# 02_J-Link.net
KiCad netlist of a schematic drawn in Altium Designer
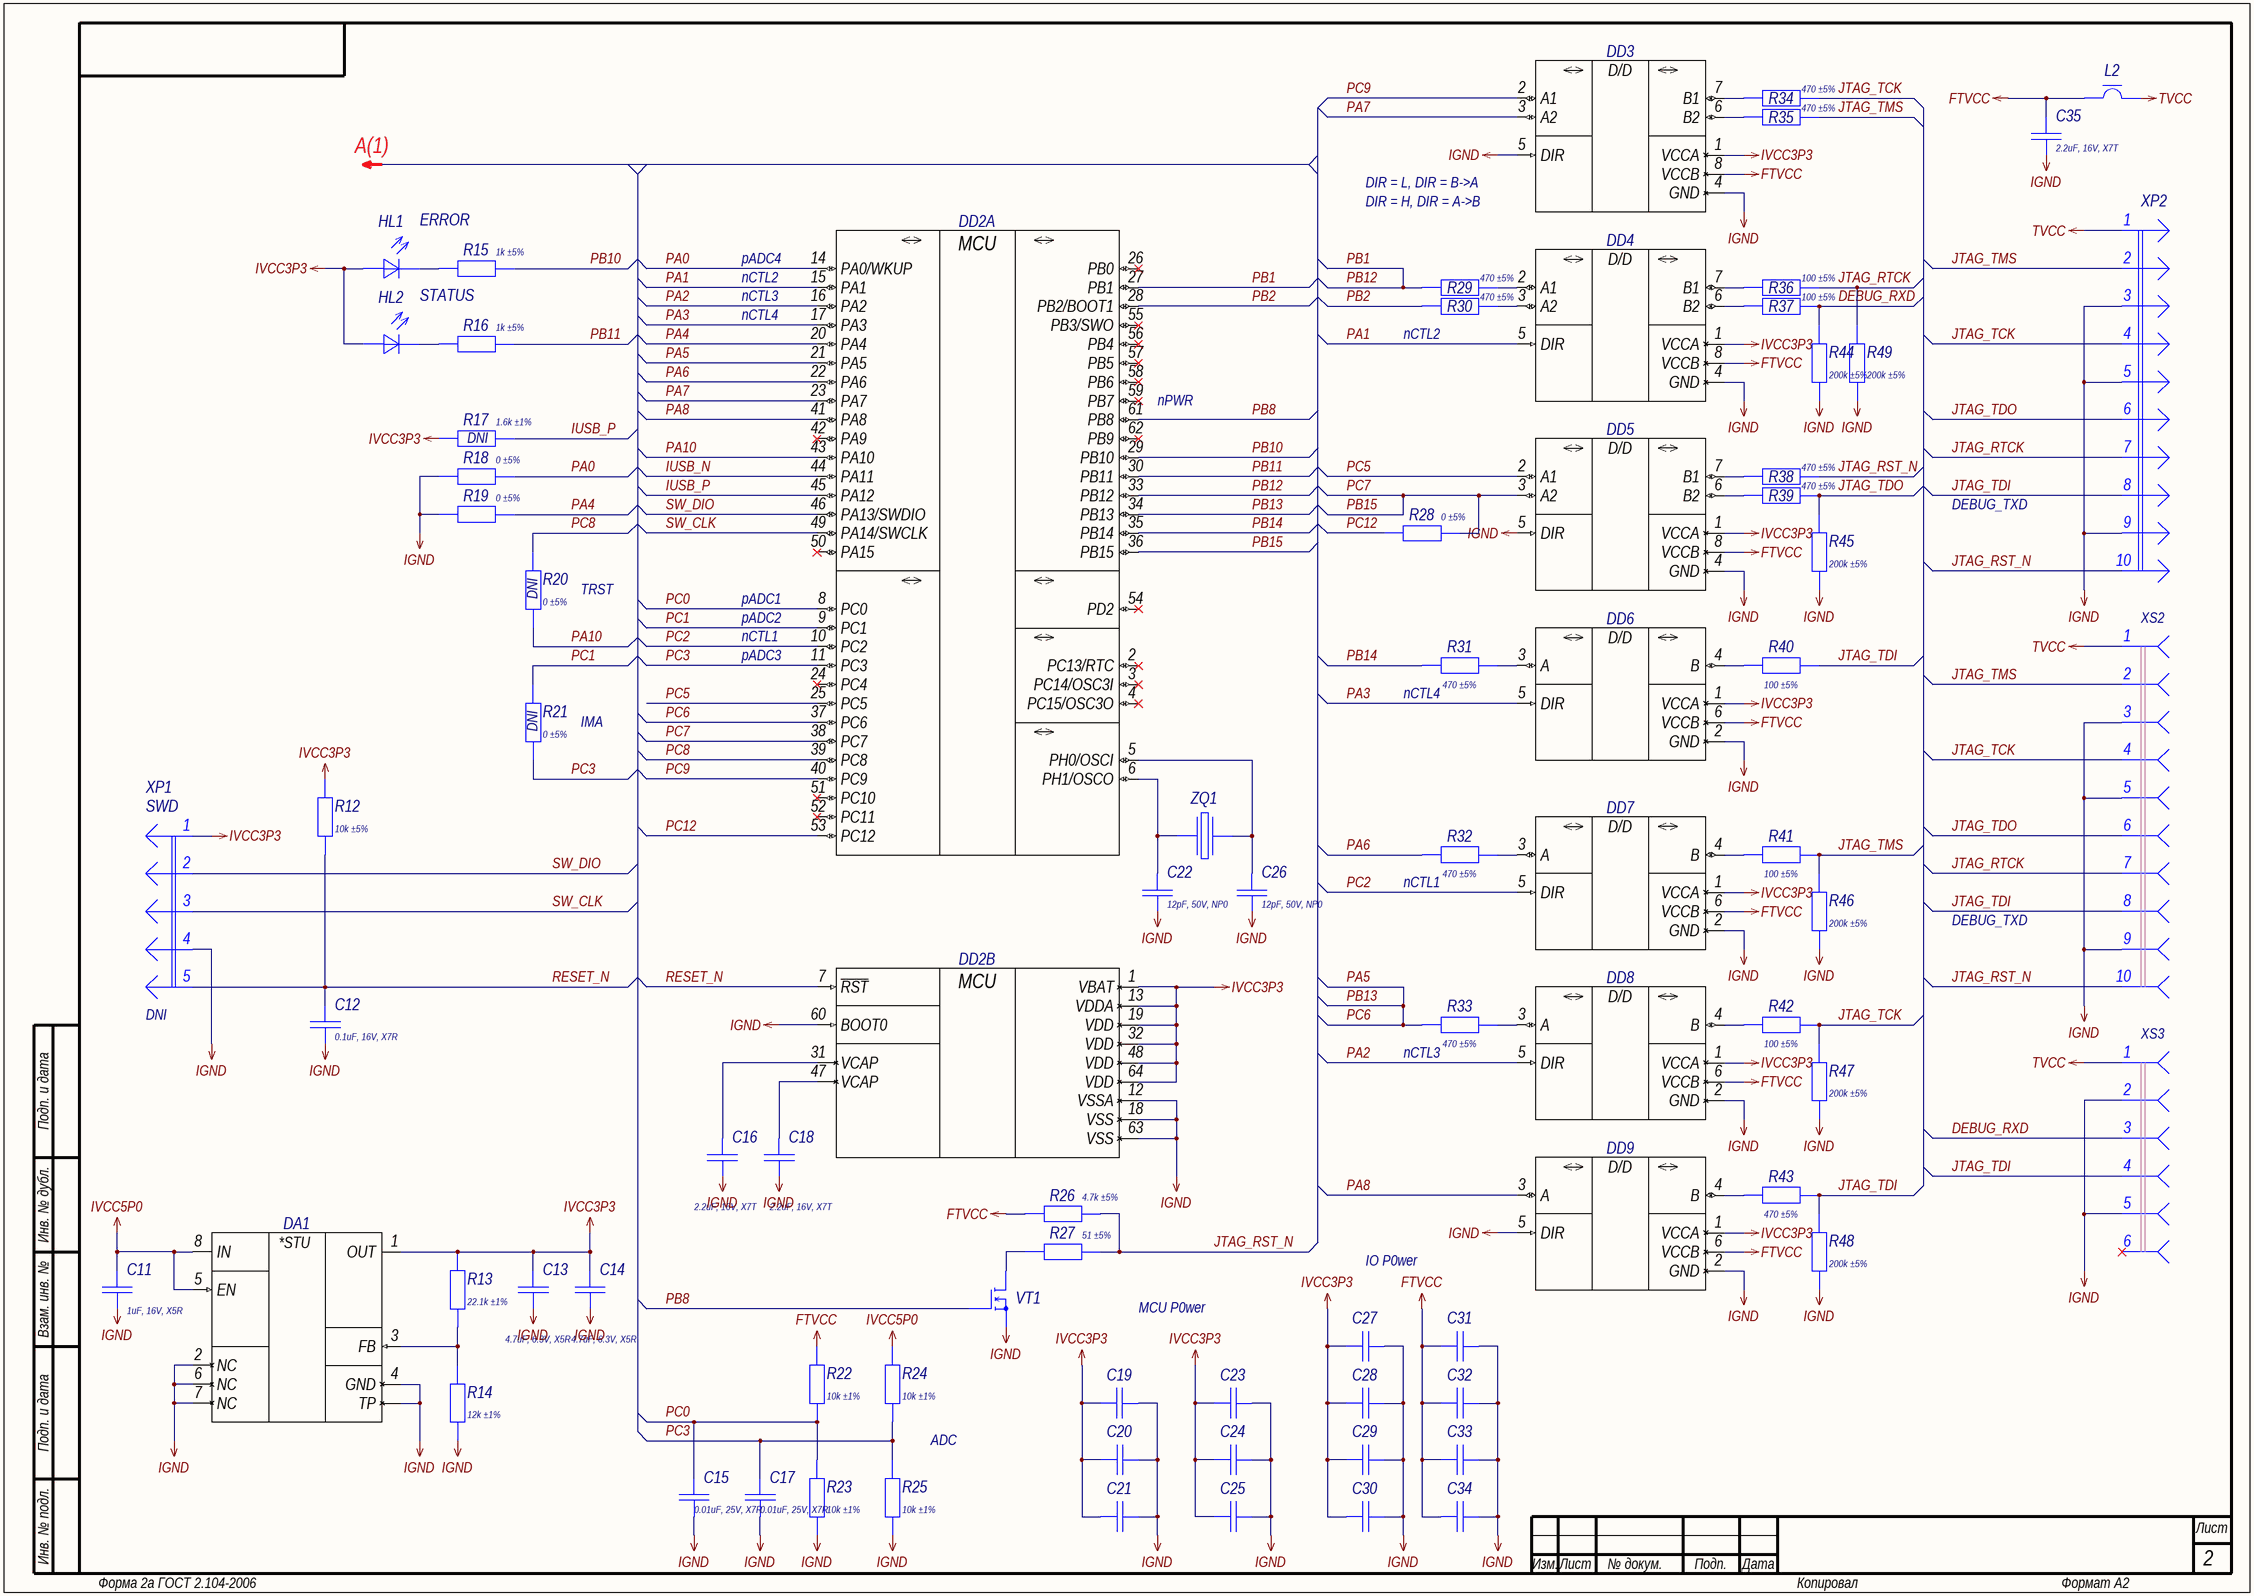
[diagram p0: 02_J-Link.SchDoc]

(export (version "E")
  (design (tool "Eeschema 10.0.6"))
  (components
    (comp (ref "C11")
      (value "Capacitor")
      (footprint "C0402_L")
      (fields
        (field (name "PART NUMBER") "GRM155R61C105KA12D")
        (field (name "VOLTAGE") "16V")
        (field (name "TOLERANCE") "±10%")
        (field (name "SCHEMATIC VALUE") "1uF, 16V, X5R")
      )
      (libsource (lib "ADLib") (part "Capacitor"))
    )
    (comp (ref "C12")
      (value "Capacitor")
      (footprint "C0402_L")
      (fields
        (field (name "PART NUMBER") "GCM155R71C104KA55D")
        (field (name "VOLTAGE") "16V")
        (field (name "TOLERANCE") "±10%")
        (field (name "SCHEMATIC VALUE") "0.1uF, 16V, X7R")
      )
      (libsource (lib "ADLib") (part "Capacitor"))
    )
    (comp (ref "C13")
      (value "Capacitor")
      (footprint "C0402_L")
      (fields
        (field (name "PART NUMBER") "GRM155R60J475ME87D")
        (field (name "VOLTAGE") "6.3V")
        (field (name "TOLERANCE") "±20%")
        (field (name "SCHEMATIC VALUE") "4.7uF, 6.3V, X5R")
      )
      (libsource (lib "ADLib") (part "Capacitor"))
    )
    (comp (ref "C14")
      (value "Capacitor")
      (footprint "C0402_L")
      (fields
        (field (name "PART NUMBER") "GRM155R60J475ME87D")
        (field (name "VOLTAGE") "6.3V")
        (field (name "TOLERANCE") "±20%")
        (field (name "SCHEMATIC VALUE") "4.7uF, 6.3V, X5R")
      )
      (libsource (lib "ADLib") (part "Capacitor"))
    )
    (comp (ref "C15")
      (value "Capacitor")
      (footprint "C0402_L")
      (fields
        (field (name "PART NUMBER") "GCM155R71E103KA37D")
        (field (name "VOLTAGE") "25V")
        (field (name "TOLERANCE") "±10%")
        (field (name "SCHEMATIC VALUE") "0.01uF, 25V, X7R")
      )
      (libsource (lib "ADLib") (part "Capacitor"))
    )
    (comp (ref "C16")
      (value "Capacitor")
      (footprint "C0402_L")
      (fields
        (field (name "PART NUMBER") "GRM155D71C225ME11D")
        (field (name "VOLTAGE") "16V")
        (field (name "TOLERANCE") "±20%")
        (field (name "SCHEMATIC VALUE") "2.2uF, 16V, X7T")
      )
      (libsource (lib "ADLib") (part "Capacitor"))
    )
    (comp (ref "C17")
      (value "Capacitor")
      (footprint "C0402_L")
      (fields
        (field (name "PART NUMBER") "GCM155R71E103KA37D")
        (field (name "VOLTAGE") "25V")
        (field (name "TOLERANCE") "±10%")
        (field (name "SCHEMATIC VALUE") "0.01uF, 25V, X7R")
      )
      (libsource (lib "ADLib") (part "Capacitor"))
    )
    (comp (ref "C18")
      (value "Capacitor")
      (footprint "C0402_L")
      (fields
        (field (name "PART NUMBER") "GRM155D71C225ME11D")
        (field (name "VOLTAGE") "16V")
        (field (name "TOLERANCE") "±20%")
        (field (name "SCHEMATIC VALUE") "2.2uF, 16V, X7T")
      )
      (libsource (lib "ADLib") (part "Capacitor"))
    )
    (comp (ref "C19")
      (value "Capacitor")
      (footprint "C0402_L")
      (fields
        (field (name "PART NUMBER") "GRM155R60J475ME87D")
        (field (name "VOLTAGE") "6.3V")
        (field (name "TOLERANCE") "±20%")
      )
      (libsource (lib "ADLib") (part "Capacitor"))
    )
    (comp (ref "C20")
      (value "Capacitor")
      (footprint "C0402_L")
      (fields
        (field (name "PART NUMBER") "GCM155R71C104KA55D")
        (field (name "VOLTAGE") "16V")
        (field (name "TOLERANCE") "±10%")
      )
      (libsource (lib "ADLib") (part "Capacitor"))
    )
    (comp (ref "C21")
      (value "Capacitor")
      (footprint "C0402_L")
      (fields
        (field (name "PART NUMBER") "GCM155R71C104KA55D")
        (field (name "VOLTAGE") "16V")
        (field (name "TOLERANCE") "±10%")
      )
      (libsource (lib "ADLib") (part "Capacitor"))
    )
    (comp (ref "C22")
      (value "Capacitor")
      (footprint "C0402_L")
      (fields
        (field (name "PART NUMBER") "GRM1555C1H120JA01D")
        (field (name "VOLTAGE") "50V")
        (field (name "TOLERANCE") "±5%")
        (field (name "SCHEMATIC VALUE") "12pF, 50V, NP0")
      )
      (libsource (lib "ADLib") (part "Capacitor"))
    )
    (comp (ref "C23")
      (value "Capacitor")
      (footprint "C0402_L")
      (fields
        (field (name "PART NUMBER") "GCM155R71C104KA55D")
        (field (name "VOLTAGE") "16V")
        (field (name "TOLERANCE") "±10%")
      )
      (libsource (lib "ADLib") (part "Capacitor"))
    )
    (comp (ref "C24")
      (value "Capacitor")
      (footprint "C0402_L")
      (fields
        (field (name "PART NUMBER") "GCM155R71C104KA55D")
        (field (name "VOLTAGE") "16V")
        (field (name "TOLERANCE") "±10%")
      )
      (libsource (lib "ADLib") (part "Capacitor"))
    )
    (comp (ref "C25")
      (value "Capacitor")
      (footprint "C0402_L")
      (fields
        (field (name "PART NUMBER") "GCM155R71C104KA55D")
        (field (name "VOLTAGE") "16V")
        (field (name "TOLERANCE") "±10%")
      )
      (libsource (lib "ADLib") (part "Capacitor"))
    )
    (comp (ref "C26")
      (value "Capacitor")
      (footprint "C0402_L")
      (fields
        (field (name "PART NUMBER") "GRM1555C1H120JA01D")
        (field (name "VOLTAGE") "50V")
        (field (name "TOLERANCE") "±5%")
        (field (name "SCHEMATIC VALUE") "12pF, 50V, NP0")
      )
      (libsource (lib "ADLib") (part "Capacitor"))
    )
    (comp (ref "C27")
      (value "Capacitor")
      (footprint "C0402_L")
      (fields
        (field (name "PART NUMBER") "GCM155R71C104KA55D")
        (field (name "VOLTAGE") "16V")
        (field (name "TOLERANCE") "±10%")
      )
      (libsource (lib "ADLib") (part "Capacitor"))
    )
    (comp (ref "C28")
      (value "Capacitor")
      (footprint "C0402_L")
      (fields
        (field (name "PART NUMBER") "GCM155R71C104KA55D")
        (field (name "VOLTAGE") "16V")
        (field (name "TOLERANCE") "±10%")
      )
      (libsource (lib "ADLib") (part "Capacitor"))
    )
    (comp (ref "C29")
      (value "Capacitor")
      (footprint "C0402_L")
      (fields
        (field (name "PART NUMBER") "GCM155R71C104KA55D")
        (field (name "VOLTAGE") "16V")
        (field (name "TOLERANCE") "±10%")
      )
      (libsource (lib "ADLib") (part "Capacitor"))
    )
    (comp (ref "C30")
      (value "Capacitor")
      (footprint "C0402_L")
      (fields
        (field (name "PART NUMBER") "GCM155R71C104KA55D")
        (field (name "VOLTAGE") "16V")
        (field (name "TOLERANCE") "±10%")
      )
      (libsource (lib "ADLib") (part "Capacitor"))
    )
    (comp (ref "C31")
      (value "Capacitor")
      (footprint "C0402_L")
      (fields
        (field (name "PART NUMBER") "GCM155R71C104KA55D")
        (field (name "VOLTAGE") "16V")
        (field (name "TOLERANCE") "±10%")
      )
      (libsource (lib "ADLib") (part "Capacitor"))
    )
    (comp (ref "C32")
      (value "Capacitor")
      (footprint "C0402_L")
      (fields
        (field (name "PART NUMBER") "GCM155R71C104KA55D")
        (field (name "VOLTAGE") "16V")
        (field (name "TOLERANCE") "±10%")
      )
      (libsource (lib "ADLib") (part "Capacitor"))
    )
    (comp (ref "C33")
      (value "Capacitor")
      (footprint "C0402_L")
      (fields
        (field (name "PART NUMBER") "GCM155R71C104KA55D")
        (field (name "VOLTAGE") "16V")
        (field (name "TOLERANCE") "±10%")
      )
      (libsource (lib "ADLib") (part "Capacitor"))
    )
    (comp (ref "C34")
      (value "Capacitor")
      (footprint "C0402_L")
      (fields
        (field (name "PART NUMBER") "GCM155R71C104KA55D")
        (field (name "VOLTAGE") "16V")
        (field (name "TOLERANCE") "±10%")
      )
      (libsource (lib "ADLib") (part "Capacitor"))
    )
    (comp (ref "C35")
      (value "Capacitor")
      (footprint "C0402_L")
      (fields
        (field (name "PART NUMBER") "GRM155D71C225ME11D")
        (field (name "VOLTAGE") "16V")
        (field (name "TOLERANCE") "±20%")
        (field (name "SCHEMATIC VALUE") "2.2uF, 16V, X7T")
      )
      (libsource (lib "ADLib") (part "Capacitor"))
    )
    (comp (ref "DA1")
      (value "TPS73701DRB")
      (footprint "VSON-8_065P300X300X100_N")
      (fields (field (name "PART NUMBER") "TPS73701DRBR") (field (name "MANUFACTURER") "Texas Instruments"))
      (libsource (lib "ADLib") (part "TPS73701DRB"))
    )
    (comp (ref "DD2")
      (value "STM32F205RxTx-Series")
      (footprint "LQFP-64_050P1000X1000X160_N")
      (fields (field (name "PART NUMBER") "STM32F205RET6") (field (name "MANUFACTURER") "STMicroelectronics"))
      (libsource (lib "ADLib") (part "STM32F205RxTx-Series"))
    )
    (comp (ref "DD3")
      (value "SN74LVC2T45DCx-Series")
      (footprint "VSSOP-8_050P200X230X090_N")
      (fields
        (field (name "PART NUMBER") "SN74LVC2T45DCUR")
        (field (name "MANUFACTURER") "Texas Instruments")
      )
      (libsource (lib "ADLib") (part "SN74LVC2T45DCx-Series"))
    )
    (comp (ref "DD4")
      (value "SN74LVC2T45DCx-Series")
      (footprint "VSSOP-8_050P200X230X090_N")
      (fields
        (field (name "PART NUMBER") "SN74LVC2T45DCUR")
        (field (name "MANUFACTURER") "Texas Instruments")
      )
      (libsource (lib "ADLib") (part "SN74LVC2T45DCx-Series"))
    )
    (comp (ref "DD5")
      (value "SN74LVC2T45DCx-Series")
      (footprint "VSSOP-8_050P200X230X090_N")
      (fields
        (field (name "PART NUMBER") "SN74LVC2T45DCUR")
        (field (name "MANUFACTURER") "Texas Instruments")
      )
      (libsource (lib "ADLib") (part "SN74LVC2T45DCx-Series"))
    )
    (comp (ref "DD6")
      (value "74LVC1T45x-Series")
      (footprint "X2-DFN-6_050P140X100X040_N")
      (fields
        (field (name "PART NUMBER") "74LVC1T45FZ4-7")
        (field (name "MANUFACTURER") "Diodes Incorporated")
      )
      (libsource (lib "ADLib") (part "74LVC1T45x-Series"))
    )
    (comp (ref "DD7")
      (value "74LVC1T45x-Series")
      (footprint "X2-DFN-6_050P140X100X040_N")
      (fields
        (field (name "PART NUMBER") "74LVC1T45FZ4-7")
        (field (name "MANUFACTURER") "Diodes Incorporated")
      )
      (libsource (lib "ADLib") (part "74LVC1T45x-Series"))
    )
    (comp (ref "DD8")
      (value "74LVC1T45x-Series")
      (footprint "X2-DFN-6_050P140X100X040_N")
      (fields
        (field (name "PART NUMBER") "74LVC1T45FZ4-7")
        (field (name "MANUFACTURER") "Diodes Incorporated")
      )
      (libsource (lib "ADLib") (part "74LVC1T45x-Series"))
    )
    (comp (ref "DD9")
      (value "74LVC1T45x-Series")
      (footprint "X2-DFN-6_050P140X100X040_N")
      (fields
        (field (name "PART NUMBER") "74LVC1T45FZ4-7")
        (field (name "MANUFACTURER") "Diodes Incorporated")
      )
      (libsource (lib "ADLib") (part "74LVC1T45x-Series"))
    )
    (comp (ref "HL1")
      (value "ERROR")
      (footprint "LD0402_L")
      (fields (field (name "PART NUMBER") "KPHHS-1005SURCK") (field (name "MANUFACTURER") "Kingbright"))
      (libsource (lib "ADLib") (part "Led-1"))
    )
    (comp (ref "HL2")
      (value "STATUS")
      (footprint "LD0402_L")
      (fields (field (name "PART NUMBER") "KPHHS-1005QBC-D-V") (field (name "MANUFACTURER") "Kingbright"))
      (libsource (lib "ADLib") (part "Led-1"))
    )
    (comp (ref "L2")
      (value "FerriteBead")
      (footprint "L0402_L")
      (fields
        (field (name "PART NUMBER") "BLM15PD121SN1D")
        (field (name "TOLERANCE") "±25%")
        (field (name "MANUFACTURER") "Murata")
      )
      (libsource (lib "ADLib") (part "FerriteBead"))
    )
    (comp (ref "R12")
      (value "Resistor")
      (footprint "R0402_L")
      (fields
        (field (name "PART NUMBER") "RC0402JR-0710KL")
        (field (name "TOLERANCE") "±5%")
        (field (name "MANUFACTURER") "Yageo")
        (field (name "SCHEMATIC VALUE") "10k ±5%")
      )
      (libsource (lib "ADLib") (part "Resistor"))
    )
    (comp (ref "R13")
      (value "Resistor")
      (footprint "R0402_L")
      (fields
        (field (name "PART NUMBER") "RC0402FR-0722K1L")
        (field (name "TOLERANCE") "±1%")
        (field (name "MANUFACTURER") "Yageo")
        (field (name "SCHEMATIC VALUE") "22.1k ±1%")
      )
      (libsource (lib "ADLib") (part "Resistor"))
    )
    (comp (ref "R14")
      (value "Resistor")
      (footprint "R0402_L")
      (fields
        (field (name "PART NUMBER") "RC0402FR-0712KL")
        (field (name "TOLERANCE") "±1%")
        (field (name "MANUFACTURER") "Yageo")
        (field (name "SCHEMATIC VALUE") "12k ±1%")
      )
      (libsource (lib "ADLib") (part "Resistor"))
    )
    (comp (ref "R15")
      (value "Resistor")
      (footprint "R0402_L")
      (fields
        (field (name "PART NUMBER") "RC0402JR-071KL")
        (field (name "TOLERANCE") "±5%")
        (field (name "MANUFACTURER") "Yageo")
        (field (name "SCHEMATIC VALUE") "1k ±5%")
      )
      (libsource (lib "ADLib") (part "Resistor"))
    )
    (comp (ref "R16")
      (value "Resistor")
      (footprint "R0402_L")
      (fields
        (field (name "PART NUMBER") "RC0402JR-071KL")
        (field (name "TOLERANCE") "±5%")
        (field (name "MANUFACTURER") "Yageo")
        (field (name "SCHEMATIC VALUE") "1k ±5%")
      )
      (libsource (lib "ADLib") (part "Resistor"))
    )
    (comp (ref "R17")
      (value "Resistor")
      (footprint "R0402_L")
      (fields
        (field (name "PART NUMBER") "RC0402FR-071K6L")
        (field (name "TOLERANCE") "±1%")
        (field (name "MANUFACTURER") "Yageo")
        (field (name "SCHEMATIC VALUE") "1.6k ±1%")
      )
      (libsource (lib "ADLib") (part "Resistor"))
    )
    (comp (ref "R18")
      (value "Resistor")
      (footprint "R0402_L")
      (fields
        (field (name "PART NUMBER") "RC0402JR-070RL")
        (field (name "TOLERANCE") "±5%")
        (field (name "MANUFACTURER") "Yageo")
        (field (name "SCHEMATIC VALUE") "0 ±5%")
      )
      (libsource (lib "ADLib") (part "Resistor"))
    )
    (comp (ref "R19")
      (value "Resistor")
      (footprint "R0402_L")
      (fields
        (field (name "PART NUMBER") "RC0402JR-070RL")
        (field (name "TOLERANCE") "±5%")
        (field (name "MANUFACTURER") "Yageo")
        (field (name "SCHEMATIC VALUE") "0 ±5%")
      )
      (libsource (lib "ADLib") (part "Resistor"))
    )
    (comp (ref "R20")
      (value "Resistor")
      (footprint "R0402_L")
      (fields
        (field (name "PART NUMBER") "RC0402JR-070RL")
        (field (name "TOLERANCE") "±5%")
        (field (name "MANUFACTURER") "Yageo")
        (field (name "SCHEMATIC VALUE") "0 ±5%")
      )
      (libsource (lib "ADLib") (part "Resistor"))
    )
    (comp (ref "R21")
      (value "Resistor")
      (footprint "R0402_L")
      (fields
        (field (name "PART NUMBER") "RC0402JR-070RL")
        (field (name "TOLERANCE") "±5%")
        (field (name "MANUFACTURER") "Yageo")
        (field (name "SCHEMATIC VALUE") "0 ±5%")
      )
      (libsource (lib "ADLib") (part "Resistor"))
    )
    (comp (ref "R22")
      (value "Resistor")
      (footprint "R0402_L")
      (fields
        (field (name "PART NUMBER") "RC0402FR-0710KL")
        (field (name "TOLERANCE") "±1%")
        (field (name "MANUFACTURER") "Yageo")
        (field (name "SCHEMATIC VALUE") "10k ±1%")
      )
      (libsource (lib "ADLib") (part "Resistor"))
    )
    (comp (ref "R23")
      (value "Resistor")
      (footprint "R0402_L")
      (fields
        (field (name "PART NUMBER") "RC0402FR-0710KL")
        (field (name "TOLERANCE") "±1%")
        (field (name "MANUFACTURER") "Yageo")
        (field (name "SCHEMATIC VALUE") "10k ±1%")
      )
      (libsource (lib "ADLib") (part "Resistor"))
    )
    (comp (ref "R24")
      (value "Resistor")
      (footprint "R0402_L")
      (fields
        (field (name "PART NUMBER") "RC0402FR-0710KL")
        (field (name "TOLERANCE") "±1%")
        (field (name "MANUFACTURER") "Yageo")
        (field (name "SCHEMATIC VALUE") "10k ±1%")
      )
      (libsource (lib "ADLib") (part "Resistor"))
    )
    (comp (ref "R25")
      (value "Resistor")
      (footprint "R0402_L")
      (fields
        (field (name "PART NUMBER") "RC0402FR-0710KL")
        (field (name "TOLERANCE") "±1%")
        (field (name "MANUFACTURER") "Yageo")
        (field (name "SCHEMATIC VALUE") "10k ±1%")
      )
      (libsource (lib "ADLib") (part "Resistor"))
    )
    (comp (ref "R26")
      (value "Resistor")
      (footprint "R0402_L")
      (fields
        (field (name "PART NUMBER") "RC0402JR-074K7L")
        (field (name "TOLERANCE") "±5%")
        (field (name "MANUFACTURER") "Yageo")
        (field (name "SCHEMATIC VALUE") "4.7k ±5%")
      )
      (libsource (lib "ADLib") (part "Resistor"))
    )
    (comp (ref "R27")
      (value "Resistor")
      (footprint "R0402_L")
      (fields
        (field (name "PART NUMBER") "RC0402JR-0751RL")
        (field (name "TOLERANCE") "±5%")
        (field (name "MANUFACTURER") "Yageo")
        (field (name "SCHEMATIC VALUE") "51 ±5%")
      )
      (libsource (lib "ADLib") (part "Resistor"))
    )
    (comp (ref "R28")
      (value "Resistor")
      (footprint "R0402_L")
      (fields
        (field (name "PART NUMBER") "RC0402JR-070RL")
        (field (name "TOLERANCE") "±5%")
        (field (name "MANUFACTURER") "Yageo")
        (field (name "SCHEMATIC VALUE") "0 ±5%")
      )
      (libsource (lib "ADLib") (part "Resistor"))
    )
    (comp (ref "R29")
      (value "Resistor")
      (footprint "R0402_L")
      (fields
        (field (name "PART NUMBER") "RC0402JR-07470RL")
        (field (name "TOLERANCE") "±5%")
        (field (name "MANUFACTURER") "Yageo")
        (field (name "SCHEMATIC VALUE") "470 ±5%")
      )
      (libsource (lib "ADLib") (part "Resistor"))
    )
    (comp (ref "R30")
      (value "Resistor")
      (footprint "R0402_L")
      (fields
        (field (name "PART NUMBER") "RC0402JR-07470RL")
        (field (name "TOLERANCE") "±5%")
        (field (name "MANUFACTURER") "Yageo")
        (field (name "SCHEMATIC VALUE") "470 ±5%")
      )
      (libsource (lib "ADLib") (part "Resistor"))
    )
    (comp (ref "R31")
      (value "Resistor")
      (footprint "R0402_L")
      (fields
        (field (name "PART NUMBER") "RC0402JR-07470RL")
        (field (name "TOLERANCE") "±5%")
        (field (name "MANUFACTURER") "Yageo")
        (field (name "SCHEMATIC VALUE") "470 ±5%")
      )
      (libsource (lib "ADLib") (part "Resistor"))
    )
    (comp (ref "R32")
      (value "Resistor")
      (footprint "R0402_L")
      (fields
        (field (name "PART NUMBER") "RC0402JR-07470RL")
        (field (name "TOLERANCE") "±5%")
        (field (name "MANUFACTURER") "Yageo")
        (field (name "SCHEMATIC VALUE") "470 ±5%")
      )
      (libsource (lib "ADLib") (part "Resistor"))
    )
    (comp (ref "R33")
      (value "Resistor")
      (footprint "R0402_L")
      (fields
        (field (name "PART NUMBER") "RC0402JR-07470RL")
        (field (name "TOLERANCE") "±5%")
        (field (name "MANUFACTURER") "Yageo")
        (field (name "SCHEMATIC VALUE") "470 ±5%")
      )
      (libsource (lib "ADLib") (part "Resistor"))
    )
    (comp (ref "R34")
      (value "Resistor")
      (footprint "R0402_L")
      (fields
        (field (name "PART NUMBER") "RC0402JR-07470RL")
        (field (name "TOLERANCE") "±5%")
        (field (name "MANUFACTURER") "Yageo")
        (field (name "SCHEMATIC VALUE") "470 ±5%")
      )
      (libsource (lib "ADLib") (part "Resistor"))
    )
    (comp (ref "R35")
      (value "Resistor")
      (footprint "R0402_L")
      (fields
        (field (name "PART NUMBER") "RC0402JR-07470RL")
        (field (name "TOLERANCE") "±5%")
        (field (name "MANUFACTURER") "Yageo")
        (field (name "SCHEMATIC VALUE") "470 ±5%")
      )
      (libsource (lib "ADLib") (part "Resistor"))
    )
    (comp (ref "R36")
      (value "Resistor")
      (footprint "R0402_L")
      (fields
        (field (name "PART NUMBER") "RC0402JR-07100RL")
        (field (name "TOLERANCE") "±5%")
        (field (name "MANUFACTURER") "Yageo")
        (field (name "SCHEMATIC VALUE") "100 ±5%")
      )
      (libsource (lib "ADLib") (part "Resistor"))
    )
    (comp (ref "R37")
      (value "Resistor")
      (footprint "R0402_L")
      (fields
        (field (name "PART NUMBER") "RC0402JR-07100RL")
        (field (name "TOLERANCE") "±5%")
        (field (name "MANUFACTURER") "Yageo")
        (field (name "SCHEMATIC VALUE") "100 ±5%")
      )
      (libsource (lib "ADLib") (part "Resistor"))
    )
    (comp (ref "R38")
      (value "Resistor")
      (footprint "R0402_L")
      (fields
        (field (name "PART NUMBER") "RC0402JR-07470RL")
        (field (name "TOLERANCE") "±5%")
        (field (name "MANUFACTURER") "Yageo")
        (field (name "SCHEMATIC VALUE") "470 ±5%")
      )
      (libsource (lib "ADLib") (part "Resistor"))
    )
    (comp (ref "R39")
      (value "Resistor")
      (footprint "R0402_L")
      (fields
        (field (name "PART NUMBER") "RC0402JR-07470RL")
        (field (name "TOLERANCE") "±5%")
        (field (name "MANUFACTURER") "Yageo")
        (field (name "SCHEMATIC VALUE") "470 ±5%")
      )
      (libsource (lib "ADLib") (part "Resistor"))
    )
    (comp (ref "R40")
      (value "Resistor")
      (footprint "R0402_L")
      (fields
        (field (name "PART NUMBER") "RC0402JR-07100RL")
        (field (name "TOLERANCE") "±5%")
        (field (name "MANUFACTURER") "Yageo")
        (field (name "SCHEMATIC VALUE") "100 ±5%")
      )
      (libsource (lib "ADLib") (part "Resistor"))
    )
    (comp (ref "R41")
      (value "Resistor")
      (footprint "R0402_L")
      (fields
        (field (name "PART NUMBER") "RC0402JR-07100RL")
        (field (name "TOLERANCE") "±5%")
        (field (name "MANUFACTURER") "Yageo")
        (field (name "SCHEMATIC VALUE") "100 ±5%")
      )
      (libsource (lib "ADLib") (part "Resistor"))
    )
    (comp (ref "R42")
      (value "Resistor")
      (footprint "R0402_L")
      (fields
        (field (name "PART NUMBER") "RC0402JR-07100RL")
        (field (name "TOLERANCE") "±5%")
        (field (name "MANUFACTURER") "Yageo")
        (field (name "SCHEMATIC VALUE") "100 ±5%")
      )
      (libsource (lib "ADLib") (part "Resistor"))
    )
    (comp (ref "R43")
      (value "Resistor")
      (footprint "R0402_L")
      (fields
        (field (name "PART NUMBER") "RC0402JR-07470RL")
        (field (name "TOLERANCE") "±5%")
        (field (name "MANUFACTURER") "Yageo")
        (field (name "SCHEMATIC VALUE") "470 ±5%")
      )
      (libsource (lib "ADLib") (part "Resistor"))
    )
    (comp (ref "R44")
      (value "Resistor")
      (footprint "R0402_L")
      (fields
        (field (name "PART NUMBER") "RC0402JR-07200KL")
        (field (name "TOLERANCE") "±5%")
        (field (name "MANUFACTURER") "Yageo")
        (field (name "SCHEMATIC VALUE") "200k ±5%")
      )
      (libsource (lib "ADLib") (part "Resistor"))
    )
    (comp (ref "R45")
      (value "Resistor")
      (footprint "R0402_L")
      (fields
        (field (name "PART NUMBER") "RC0402JR-07200KL")
        (field (name "TOLERANCE") "±5%")
        (field (name "MANUFACTURER") "Yageo")
        (field (name "SCHEMATIC VALUE") "200k ±5%")
      )
      (libsource (lib "ADLib") (part "Resistor"))
    )
    (comp (ref "R46")
      (value "Resistor")
      (footprint "R0402_L")
      (fields
        (field (name "PART NUMBER") "RC0402JR-07200KL")
        (field (name "TOLERANCE") "±5%")
        (field (name "MANUFACTURER") "Yageo")
        (field (name "SCHEMATIC VALUE") "200k ±5%")
      )
      (libsource (lib "ADLib") (part "Resistor"))
    )
    (comp (ref "R47")
      (value "Resistor")
      (footprint "R0402_L")
      (fields
        (field (name "PART NUMBER") "RC0402JR-07200KL")
        (field (name "TOLERANCE") "±5%")
        (field (name "MANUFACTURER") "Yageo")
        (field (name "SCHEMATIC VALUE") "200k ±5%")
      )
      (libsource (lib "ADLib") (part "Resistor"))
    )
    (comp (ref "R48")
      (value "Resistor")
      (footprint "R0402_L")
      (fields
        (field (name "PART NUMBER") "RC0402JR-07200KL")
        (field (name "TOLERANCE") "±5%")
        (field (name "MANUFACTURER") "Yageo")
        (field (name "SCHEMATIC VALUE") "200k ±5%")
      )
      (libsource (lib "ADLib") (part "Resistor"))
    )
    (comp (ref "R49")
      (value "Resistor")
      (footprint "R0402_L")
      (fields
        (field (name "PART NUMBER") "RC0402JR-07200KL")
        (field (name "TOLERANCE") "±5%")
        (field (name "MANUFACTURER") "Yageo")
        (field (name "SCHEMATIC VALUE") "200k ±5%")
      )
      (libsource (lib "ADLib") (part "Resistor"))
    )
    (comp (ref "VT1")
      (value "MOSFET-N_32")
      (footprint "SOT-883B_035P060X100X040_N")
      (fields (field (name "PART NUMBER") "NX3008NBKMB") (field (name "MANUFACTURER") "NXP Semiconductors"))
      (libsource (lib "ADLib") (part "MOSFET-N_32"))
    )
    (comp (ref "XP1")
      (value "SWD")
      (footprint "PLS-5")
      (fields (field (name "PART NUMBER") "PLS-5"))
      (libsource (lib "ADLib") (part "Con-5-M"))
    )
    (comp (ref "XP2")
      (value "JTAG")
      (footprint "IDC-10MR")
      (fields (field (name "PART NUMBER") "IDC-10MR"))
      (libsource (lib "ADLib") (part "Con-10-M"))
    )
    (comp (ref "XS2")
      (value "JTAG-FFC")
      (footprint "XF2M-1015-1A")
      (fields (field (name "PART NUMBER") "XF2M-1015-1A") (field (name "MANUFACTURER") "Omron Electronics"))
      (libsource (lib "ADLib") (part "Con-10-F_S"))
    )
    (comp (ref "XS3")
      (value "DEBUG-FFC")
      (footprint "XF2M-0615-1A")
      (fields (field (name "PART NUMBER") "XF2M-0615-1A") (field (name "MANUFACTURER") "Omron Electronics"))
      (libsource (lib "ADLib") (part "Con-6-F_S"))
    )
    (comp (ref "ZQ1")
      (value "Crystal")
      (footprint "SMD 5x3.2mm")
      (fields (field (name "PART NUMBER") "AB-12.000MALE-T"))
      (libsource (lib "ADLib") (part "Crystal"))
    )
  )
  (nets
    (net (code "1") (name "/DEBUG_RXD") (class "Default")
      (node (ref "R37") (pin "2") (pinfunction "2_2") (pintype "passive"))
      (node (ref "R44") (pin "2") (pinfunction "2_2") (pintype "passive"))
      (node (ref "XS3") (pin "3") (pintype "passive"))
    )
    (net (code "2") (name "/IUSB_N") (class "Default")
      (node (ref "DD2") (pin "44") (pinfunction "PA11_44") (pintype "bidirectional"))
    )
    (net (code "3") (name "/IUSB_P") (class "Default")
      (node (ref "DD2") (pin "45") (pinfunction "PA12_45") (pintype "bidirectional"))
      (node (ref "R17") (pin "2") (pinfunction "2_2") (pintype "passive"))
    )
    (net (code "4") (name "/JTAG_RST_N") (class "Default")
      (node (ref "R26") (pin "2") (pinfunction "2_2") (pintype "passive"))
      (node (ref "R27") (pin "2") (pinfunction "2_2") (pintype "passive"))
      (node (ref "R38") (pin "2") (pinfunction "2_2") (pintype "passive"))
      (node (ref "XP2") (pin "10") (pintype "passive"))
      (node (ref "XS2") (pin "10") (pintype "passive"))
    )
    (net (code "5") (name "/JTAG_RTCK") (class "Default")
      (node (ref "R36") (pin "2") (pinfunction "2_2") (pintype "passive"))
      (node (ref "R49") (pin "2") (pinfunction "2_2") (pintype "passive"))
      (node (ref "XP2") (pin "7") (pintype "passive"))
      (node (ref "XS2") (pin "7") (pintype "passive"))
    )
    (net (code "6") (name "/JTAG_TCK") (class "Default")
      (node (ref "R34") (pin "2") (pinfunction "2_2") (pintype "passive"))
      (node (ref "R42") (pin "2") (pinfunction "2_2") (pintype "passive"))
      (node (ref "R47") (pin "2") (pinfunction "2_2") (pintype "passive"))
      (node (ref "XP2") (pin "4") (pintype "passive"))
      (node (ref "XS2") (pin "4") (pintype "passive"))
    )
    (net (code "7") (name "/JTAG_TDI") (class "Default")
      (node (ref "R40") (pin "2") (pinfunction "2_2") (pintype "passive"))
      (node (ref "R43") (pin "2") (pinfunction "2_2") (pintype "passive"))
      (node (ref "R48") (pin "2") (pinfunction "2_2") (pintype "passive"))
      (node (ref "XP2") (pin "8") (pintype "passive"))
      (node (ref "XS2") (pin "8") (pintype "passive"))
      (node (ref "XS3") (pin "4") (pintype "passive"))
    )
    (net (code "8") (name "/JTAG_TDO") (class "Default")
      (node (ref "R39") (pin "2") (pinfunction "2_2") (pintype "passive"))
      (node (ref "R45") (pin "2") (pinfunction "2_2") (pintype "passive"))
      (node (ref "XP2") (pin "6") (pintype "passive"))
      (node (ref "XS2") (pin "6") (pintype "passive"))
    )
    (net (code "9") (name "/JTAG_TMS") (class "Default")
      (node (ref "R35") (pin "2") (pinfunction "2_2") (pintype "passive"))
      (node (ref "R41") (pin "2") (pinfunction "2_2") (pintype "passive"))
      (node (ref "R46") (pin "2") (pinfunction "2_2") (pintype "passive"))
      (node (ref "XP2") (pin "2") (pintype "passive"))
      (node (ref "XS2") (pin "2") (pintype "passive"))
    )
    (net (code "10") (name "/PA0") (class "Default")
      (node (ref "DD2") (pin "14") (pinfunction "PA0/WKUP_14") (pintype "bidirectional"))
      (node (ref "R18") (pin "2") (pinfunction "2_2") (pintype "passive"))
    )
    (net (code "11") (name "/PA1") (class "Default")
      (node (ref "DD2") (pin "15") (pinfunction "PA1_15") (pintype "bidirectional"))
      (node (ref "DD4") (pin "5") (pinfunction "DIR_5") (pintype "input"))
    )
    (net (code "12") (name "/PA2") (class "Default")
      (node (ref "DD2") (pin "16") (pinfunction "PA2_16") (pintype "bidirectional"))
      (node (ref "DD8") (pin "5") (pinfunction "DIR_5") (pintype "input"))
    )
    (net (code "13") (name "/PA3") (class "Default")
      (node (ref "DD2") (pin "17") (pinfunction "PA3_17") (pintype "bidirectional"))
      (node (ref "DD6") (pin "5") (pinfunction "DIR_5") (pintype "input"))
    )
    (net (code "14") (name "/PA4") (class "Default")
      (node (ref "DD2") (pin "20") (pinfunction "PA4_20") (pintype "bidirectional"))
      (node (ref "R19") (pin "2") (pinfunction "2_2") (pintype "passive"))
    )
    (net (code "15") (name "/PA5") (class "Default")
      (node (ref "DD2") (pin "21") (pinfunction "PA5_21") (pintype "bidirectional"))
      (node (ref "DD2") (pin "34") (pinfunction "PB13_34") (pintype "bidirectional"))
      (node (ref "DD2") (pin "37") (pinfunction "PC6_37") (pintype "bidirectional"))
      (node (ref "R33") (pin "1") (pinfunction "1_1") (pintype "passive"))
    )
    (net (code "16") (name "/PA6") (class "Default")
      (node (ref "DD2") (pin "22") (pinfunction "PA6_22") (pintype "bidirectional"))
      (node (ref "R32") (pin "1") (pinfunction "1_1") (pintype "passive"))
    )
    (net (code "17") (name "/PA7") (class "Default")
      (node (ref "DD2") (pin "23") (pinfunction "PA7_23") (pintype "bidirectional"))
      (node (ref "DD3") (pin "3") (pinfunction "A2_3") (pintype "bidirectional"))
    )
    (net (code "18") (name "/PA8") (class "Default")
      (node (ref "DD2") (pin "41") (pinfunction "PA8_41") (pintype "bidirectional"))
      (node (ref "DD9") (pin "3") (pinfunction "A_3") (pintype "bidirectional"))
    )
    (net (code "19") (name "/PA10") (class "Default")
      (node (ref "DD2") (pin "43") (pinfunction "PA10_43") (pintype "bidirectional"))
      (node (ref "R20") (pin "1") (pinfunction "1_1") (pintype "passive"))
    )
    (net (code "20") (name "/PB1") (class "Default")
      (node (ref "DD2") (pin "27") (pinfunction "PB1_27") (pintype "bidirectional"))
      (node (ref "DD2") (pin "33") (pinfunction "PB12_33") (pintype "bidirectional"))
      (node (ref "R29") (pin "1") (pinfunction "1_1") (pintype "passive"))
    )
    (net (code "21") (name "/PB2") (class "Default")
      (node (ref "DD2") (pin "28") (pinfunction "PB2/BOOT1_28") (pintype "bidirectional"))
      (node (ref "R30") (pin "1") (pinfunction "1_1") (pintype "passive"))
    )
    (net (code "22") (name "/PB8") (class "Default")
      (node (ref "DD2") (pin "61") (pinfunction "PB8_61") (pintype "bidirectional"))
      (node (ref "VT1") (pin "1") (pinfunction "G_1") (pintype "passive"))
    )
    (net (code "23") (name "/PB10") (class "Default")
      (node (ref "DD2") (pin "29") (pinfunction "PB10_29") (pintype "bidirectional"))
      (node (ref "R15") (pin "2") (pinfunction "2_2") (pintype "passive"))
    )
    (net (code "24") (name "/PB11") (class "Default")
      (node (ref "DD2") (pin "30") (pinfunction "PB11_30") (pintype "bidirectional"))
      (node (ref "R16") (pin "2") (pinfunction "2_2") (pintype "passive"))
    )
    (net (code "25") (name "/PB14") (class "Default")
      (node (ref "DD2") (pin "35") (pinfunction "PB14_35") (pintype "bidirectional"))
      (node (ref "R31") (pin "1") (pinfunction "1_1") (pintype "passive"))
    )
    (net (code "26") (name "/PB15") (class "Default")
      (node (ref "DD2") (pin "36") (pinfunction "PB15_36") (pintype "bidirectional"))
      (node (ref "DD2") (pin "38") (pinfunction "PC7_38") (pintype "bidirectional"))
      (node (ref "DD5") (pin "3") (pinfunction "A2_3") (pintype "bidirectional"))
      (node (ref "R28") (pin "2") (pinfunction "2_2") (pintype "passive"))
    )
    (net (code "27") (name "/PC0") (class "Default")
      (node (ref "C15") (pin "1") (pinfunction "1_1") (pintype "passive"))
      (node (ref "DD2") (pin "8") (pinfunction "PC0_8") (pintype "bidirectional"))
      (node (ref "R22") (pin "1") (pinfunction "1_1") (pintype "passive"))
      (node (ref "R23") (pin "2") (pinfunction "2_2") (pintype "passive"))
    )
    (net (code "28") (name "/PC1") (class "Default")
      (node (ref "DD2") (pin "9") (pinfunction "PC1_9") (pintype "bidirectional"))
      (node (ref "R21") (pin "2") (pinfunction "2_2") (pintype "passive"))
    )
    (net (code "29") (name "/PC2") (class "Default")
      (node (ref "DD2") (pin "10") (pinfunction "PC2_10") (pintype "bidirectional"))
      (node (ref "DD7") (pin "5") (pinfunction "DIR_5") (pintype "input"))
    )
    (net (code "30") (name "/PC3") (class "Default")
      (node (ref "C17") (pin "1") (pinfunction "1_1") (pintype "passive"))
      (node (ref "DD2") (pin "11") (pinfunction "PC3_11") (pintype "bidirectional"))
      (node (ref "R21") (pin "1") (pinfunction "1_1") (pintype "passive"))
      (node (ref "R24") (pin "1") (pinfunction "1_1") (pintype "passive"))
      (node (ref "R25") (pin "2") (pinfunction "2_2") (pintype "passive"))
    )
    (net (code "31") (name "/PC5") (class "Default")
      (node (ref "DD2") (pin "25") (pinfunction "PC5_25") (pintype "bidirectional"))
      (node (ref "DD5") (pin "2") (pinfunction "A1_2") (pintype "bidirectional"))
    )
    (net (code "32") (name "/PC8") (class "Default")
      (node (ref "DD2") (pin "39") (pinfunction "PC8_39") (pintype "bidirectional"))
      (node (ref "R20") (pin "2") (pinfunction "2_2") (pintype "passive"))
    )
    (net (code "33") (name "/PC9") (class "Default")
      (node (ref "DD2") (pin "40") (pinfunction "PC9_40") (pintype "bidirectional"))
      (node (ref "DD3") (pin "2") (pinfunction "A1_2") (pintype "bidirectional"))
    )
    (net (code "34") (name "/PC12") (class "Default")
      (node (ref "DD2") (pin "53") (pinfunction "PC12_53") (pintype "bidirectional"))
      (node (ref "R28") (pin "1") (pinfunction "1_1") (pintype "passive"))
    )
    (net (code "35") (name "/RESET_N") (class "Default")
      (node (ref "C12") (pin "1") (pinfunction "1_1") (pintype "passive"))
      (node (ref "DD2") (pin "7") (pinfunction "~{RST}_7") (pintype "input"))
      (node (ref "R12") (pin "1") (pinfunction "1_1") (pintype "passive"))
      (node (ref "XP1") (pin "5") (pintype "passive"))
    )
    (net (code "36") (name "/SW_CLK") (class "Default")
      (node (ref "DD2") (pin "49") (pinfunction "PA14/SWCLK_49") (pintype "bidirectional"))
      (node (ref "XP1") (pin "3") (pintype "passive"))
    )
    (net (code "37") (name "/SW_DIO") (class "Default")
      (node (ref "DD2") (pin "46") (pinfunction "PA13/SWDIO_46") (pintype "bidirectional"))
      (node (ref "XP1") (pin "2") (pintype "passive"))
    )
    (net (code "38") (name "FTVCC") (class "Default")
      (node (ref "C31") (pin "1") (pinfunction "1_1") (pintype "passive"))
      (node (ref "C32") (pin "1") (pinfunction "1_1") (pintype "passive"))
      (node (ref "C33") (pin "1") (pinfunction "1_1") (pintype "passive"))
      (node (ref "C34") (pin "1") (pinfunction "1_1") (pintype "passive"))
      (node (ref "C35") (pin "2") (pinfunction "2_2") (pintype "passive"))
      (node (ref "DD3") (pin "8") (pinfunction "VCCB_8") (pintype "power_in"))
      (node (ref "DD4") (pin "8") (pinfunction "VCCB_8") (pintype "power_in"))
      (node (ref "DD5") (pin "8") (pinfunction "VCCB_8") (pintype "power_in"))
      (node (ref "DD6") (pin "6") (pinfunction "VCCB_6") (pintype "power_in"))
      (node (ref "DD7") (pin "6") (pinfunction "VCCB_6") (pintype "power_in"))
      (node (ref "DD8") (pin "6") (pinfunction "VCCB_6") (pintype "power_in"))
      (node (ref "DD9") (pin "6") (pinfunction "VCCB_6") (pintype "power_in"))
      (node (ref "L2") (pin "1") (pinfunction "1_1") (pintype "passive"))
      (node (ref "R22") (pin "2") (pinfunction "2_2") (pintype "passive"))
      (node (ref "R26") (pin "1") (pinfunction "1_1") (pintype "passive"))
    )
    (net (code "39") (name "IGND") (class "Default")
      (node (ref "C11") (pin "1") (pinfunction "1_1") (pintype "passive"))
      (node (ref "C12") (pin "2") (pinfunction "2_2") (pintype "passive"))
      (node (ref "C13") (pin "1") (pinfunction "1_1") (pintype "passive"))
      (node (ref "C14") (pin "1") (pinfunction "1_1") (pintype "passive"))
      (node (ref "C15") (pin "2") (pinfunction "2_2") (pintype "passive"))
      (node (ref "C16") (pin "1") (pinfunction "1_1") (pintype "passive"))
      (node (ref "C17") (pin "2") (pinfunction "2_2") (pintype "passive"))
      (node (ref "C18") (pin "1") (pinfunction "1_1") (pintype "passive"))
      (node (ref "C19") (pin "1") (pinfunction "1_1") (pintype "passive"))
      (node (ref "C20") (pin "2") (pinfunction "2_2") (pintype "passive"))
      (node (ref "C21") (pin "2") (pinfunction "2_2") (pintype "passive"))
      (node (ref "C22") (pin "1") (pinfunction "1_1") (pintype "passive"))
      (node (ref "C23") (pin "2") (pinfunction "2_2") (pintype "passive"))
      (node (ref "C24") (pin "2") (pinfunction "2_2") (pintype "passive"))
      (node (ref "C25") (pin "2") (pinfunction "2_2") (pintype "passive"))
      (node (ref "C26") (pin "1") (pinfunction "1_1") (pintype "passive"))
      (node (ref "C27") (pin "2") (pinfunction "2_2") (pintype "passive"))
      (node (ref "C28") (pin "2") (pinfunction "2_2") (pintype "passive"))
      (node (ref "C29") (pin "2") (pinfunction "2_2") (pintype "passive"))
      (node (ref "C30") (pin "2") (pinfunction "2_2") (pintype "passive"))
      (node (ref "C31") (pin "2") (pinfunction "2_2") (pintype "passive"))
      (node (ref "C32") (pin "2") (pinfunction "2_2") (pintype "passive"))
      (node (ref "C33") (pin "2") (pinfunction "2_2") (pintype "passive"))
      (node (ref "C34") (pin "2") (pinfunction "2_2") (pintype "passive"))
      (node (ref "C35") (pin "1") (pinfunction "1_1") (pintype "passive"))
      (node (ref "DA1") (pin "2") (pinfunction "NC_2") (pintype "passive"))
      (node (ref "DA1") (pin "4") (pinfunction "GND_4") (pintype "power_in"))
      (node (ref "DA1") (pin "6") (pinfunction "NC_6") (pintype "passive"))
      (node (ref "DA1") (pin "7") (pinfunction "NC_7") (pintype "passive"))
      (node (ref "DA1") (pin "TP") (pinfunction "TP_TP") (pintype "passive"))
      (node (ref "DD2") (pin "12") (pinfunction "VSSA_12") (pintype "power_in"))
      (node (ref "DD2") (pin "18") (pinfunction "VSS_18") (pintype "power_in"))
      (node (ref "DD2") (pin "60") (pinfunction "BOOT0_60") (pintype "input"))
      (node (ref "DD2") (pin "63") (pinfunction "VSS_63") (pintype "power_in"))
      (node (ref "DD3") (pin "4") (pinfunction "GND_4") (pintype "power_in"))
      (node (ref "DD3") (pin "5") (pinfunction "DIR_5") (pintype "input"))
      (node (ref "DD4") (pin "4") (pinfunction "GND_4") (pintype "power_in"))
      (node (ref "DD5") (pin "4") (pinfunction "GND_4") (pintype "power_in"))
      (node (ref "DD5") (pin "5") (pinfunction "DIR_5") (pintype "input"))
      (node (ref "DD6") (pin "2") (pinfunction "GND_2") (pintype "power_in"))
      (node (ref "DD7") (pin "2") (pinfunction "GND_2") (pintype "power_in"))
      (node (ref "DD8") (pin "2") (pinfunction "GND_2") (pintype "power_in"))
      (node (ref "DD9") (pin "2") (pinfunction "GND_2") (pintype "power_in"))
      (node (ref "DD9") (pin "5") (pinfunction "DIR_5") (pintype "input"))
      (node (ref "R14") (pin "1") (pinfunction "1_1") (pintype "passive"))
      (node (ref "R18") (pin "1") (pinfunction "1_1") (pintype "passive"))
      (node (ref "R19") (pin "1") (pinfunction "1_1") (pintype "passive"))
      (node (ref "R23") (pin "1") (pinfunction "1_1") (pintype "passive"))
      (node (ref "R25") (pin "1") (pinfunction "1_1") (pintype "passive"))
      (node (ref "R44") (pin "1") (pinfunction "1_1") (pintype "passive"))
      (node (ref "R45") (pin "1") (pinfunction "1_1") (pintype "passive"))
      (node (ref "R46") (pin "1") (pinfunction "1_1") (pintype "passive"))
      (node (ref "R47") (pin "1") (pinfunction "1_1") (pintype "passive"))
      (node (ref "R48") (pin "1") (pinfunction "1_1") (pintype "passive"))
      (node (ref "R49") (pin "1") (pinfunction "1_1") (pintype "passive"))
      (node (ref "VT1") (pin "2") (pinfunction "S_2") (pintype "passive"))
      (node (ref "XP1") (pin "4") (pintype "passive"))
      (node (ref "XP2") (pin "3") (pintype "passive"))
      (node (ref "XP2") (pin "5") (pintype "passive"))
      (node (ref "XP2") (pin "9") (pintype "passive"))
      (node (ref "XS2") (pin "3") (pintype "passive"))
      (node (ref "XS2") (pin "5") (pintype "passive"))
      (node (ref "XS2") (pin "9") (pintype "passive"))
      (node (ref "XS3") (pin "2") (pintype "passive"))
      (node (ref "XS3") (pin "5") (pintype "passive"))
    )
    (net (code "40") (name "IVCC3P3") (class "Default")
      (node (ref "C13") (pin "2") (pinfunction "2_2") (pintype "passive"))
      (node (ref "C14") (pin "2") (pinfunction "2_2") (pintype "passive"))
      (node (ref "C19") (pin "2") (pinfunction "2_2") (pintype "passive"))
      (node (ref "C20") (pin "1") (pinfunction "1_1") (pintype "passive"))
      (node (ref "C21") (pin "1") (pinfunction "1_1") (pintype "passive"))
      (node (ref "C23") (pin "1") (pinfunction "1_1") (pintype "passive"))
      (node (ref "C24") (pin "1") (pinfunction "1_1") (pintype "passive"))
      (node (ref "C25") (pin "1") (pinfunction "1_1") (pintype "passive"))
      (node (ref "C27") (pin "1") (pinfunction "1_1") (pintype "passive"))
      (node (ref "C28") (pin "1") (pinfunction "1_1") (pintype "passive"))
      (node (ref "C29") (pin "1") (pinfunction "1_1") (pintype "passive"))
      (node (ref "C30") (pin "1") (pinfunction "1_1") (pintype "passive"))
      (node (ref "DA1") (pin "1") (pinfunction "OUT_1") (pintype "power_in"))
      (node (ref "DD2") (pin "1") (pinfunction "VBAT_1") (pintype "power_in"))
      (node (ref "DD2") (pin "13") (pinfunction "VDDA_13") (pintype "power_in"))
      (node (ref "DD2") (pin "19") (pinfunction "VDD_19") (pintype "power_in"))
      (node (ref "DD2") (pin "32") (pinfunction "VDD_32") (pintype "power_in"))
      (node (ref "DD2") (pin "48") (pinfunction "VDD_48") (pintype "power_in"))
      (node (ref "DD2") (pin "64") (pinfunction "VDD_64") (pintype "power_in"))
      (node (ref "DD3") (pin "1") (pinfunction "VCCA_1") (pintype "power_in"))
      (node (ref "DD4") (pin "1") (pinfunction "VCCA_1") (pintype "power_in"))
      (node (ref "DD5") (pin "1") (pinfunction "VCCA_1") (pintype "power_in"))
      (node (ref "DD6") (pin "1") (pinfunction "VCCA_1") (pintype "power_in"))
      (node (ref "DD7") (pin "1") (pinfunction "VCCA_1") (pintype "power_in"))
      (node (ref "DD8") (pin "1") (pinfunction "VCCA_1") (pintype "power_in"))
      (node (ref "DD9") (pin "1") (pinfunction "VCCA_1") (pintype "power_in"))
      (node (ref "HL1") (pin "1") (pinfunction "А_1") (pintype "passive"))
      (node (ref "HL2") (pin "1") (pinfunction "А_1") (pintype "passive"))
      (node (ref "R12") (pin "2") (pinfunction "2_2") (pintype "passive"))
      (node (ref "R13") (pin "2") (pinfunction "2_2") (pintype "passive"))
      (node (ref "R17") (pin "1") (pinfunction "1_1") (pintype "passive"))
      (node (ref "XP1") (pin "1") (pintype "passive"))
    )
    (net (code "41") (name "IVCC5P0") (class "Default")
      (node (ref "C11") (pin "2") (pinfunction "2_2") (pintype "passive"))
      (node (ref "DA1") (pin "5") (pinfunction "EN_5") (pintype "input"))
      (node (ref "DA1") (pin "8") (pinfunction "IN_8") (pintype "power_in"))
      (node (ref "R24") (pin "2") (pinfunction "2_2") (pintype "passive"))
    )
    (net (code "42") (name "Net-(C16-Pad2)") (class "Default")
      (node (ref "C16") (pin "2") (pinfunction "2_2") (pintype "passive"))
      (node (ref "DD2") (pin "31") (pinfunction "VCAP_31") (pintype "power_in"))
    )
    (net (code "43") (name "Net-(C18-Pad2)") (class "Default")
      (node (ref "C18") (pin "2") (pinfunction "2_2") (pintype "passive"))
      (node (ref "DD2") (pin "47") (pinfunction "VCAP_47") (pintype "power_in"))
    )
    (net (code "44") (name "Net-(DA1-FB)") (class "Default")
      (node (ref "DA1") (pin "3") (pinfunction "FB_3") (pintype "input"))
      (node (ref "R13") (pin "1") (pinfunction "1_1") (pintype "passive"))
      (node (ref "R14") (pin "2") (pinfunction "2_2") (pintype "passive"))
    )
    (net (code "45") (name "Net-(DD2A-PH0{slash}OSCI)") (class "Default")
      (node (ref "C26") (pin "2") (pinfunction "2_2") (pintype "passive"))
      (node (ref "DD2") (pin "5") (pinfunction "PH0/OSCI_5") (pintype "bidirectional"))
      (node (ref "ZQ1") (pin "3") (pinfunction "3_3") (pintype "passive"))
    )
    (net (code "46") (name "Net-(DD2A-PH1{slash}OSCO)") (class "Default")
      (node (ref "C22") (pin "2") (pinfunction "2_2") (pintype "passive"))
      (node (ref "DD2") (pin "6") (pinfunction "PH1/OSCO_6") (pintype "bidirectional"))
      (node (ref "ZQ1") (pin "1") (pinfunction "1_1") (pintype "passive"))
    )
    (net (code "47") (name "Net-(DD3-B1)") (class "Default")
      (node (ref "DD3") (pin "7") (pinfunction "B1_7") (pintype "bidirectional"))
      (node (ref "R34") (pin "1") (pinfunction "1_1") (pintype "passive"))
    )
    (net (code "48") (name "Net-(DD3-B2)") (class "Default")
      (node (ref "DD3") (pin "6") (pinfunction "B2_6") (pintype "bidirectional"))
      (node (ref "R35") (pin "1") (pinfunction "1_1") (pintype "passive"))
    )
    (net (code "49") (name "Net-(DD4-A1)") (class "Default")
      (node (ref "DD4") (pin "2") (pinfunction "A1_2") (pintype "bidirectional"))
      (node (ref "R29") (pin "2") (pinfunction "2_2") (pintype "passive"))
    )
    (net (code "50") (name "Net-(DD4-A2)") (class "Default")
      (node (ref "DD4") (pin "3") (pinfunction "A2_3") (pintype "bidirectional"))
      (node (ref "R30") (pin "2") (pinfunction "2_2") (pintype "passive"))
    )
    (net (code "51") (name "Net-(DD4-B1)") (class "Default")
      (node (ref "DD4") (pin "7") (pinfunction "B1_7") (pintype "bidirectional"))
      (node (ref "R36") (pin "1") (pinfunction "1_1") (pintype "passive"))
    )
    (net (code "52") (name "Net-(DD4-B2)") (class "Default")
      (node (ref "DD4") (pin "6") (pinfunction "B2_6") (pintype "bidirectional"))
      (node (ref "R37") (pin "1") (pinfunction "1_1") (pintype "passive"))
    )
    (net (code "53") (name "Net-(DD5-B1)") (class "Default")
      (node (ref "DD5") (pin "7") (pinfunction "B1_7") (pintype "bidirectional"))
      (node (ref "R38") (pin "1") (pinfunction "1_1") (pintype "passive"))
    )
    (net (code "54") (name "Net-(DD5-B2)") (class "Default")
      (node (ref "DD5") (pin "6") (pinfunction "B2_6") (pintype "bidirectional"))
      (node (ref "R39") (pin "1") (pinfunction "1_1") (pintype "passive"))
    )
    (net (code "55") (name "Net-(DD6-A)") (class "Default")
      (node (ref "DD6") (pin "3") (pinfunction "A_3") (pintype "bidirectional"))
      (node (ref "R31") (pin "2") (pinfunction "2_2") (pintype "passive"))
    )
    (net (code "56") (name "Net-(DD6-B)") (class "Default")
      (node (ref "DD6") (pin "4") (pinfunction "B_4") (pintype "bidirectional"))
      (node (ref "R40") (pin "1") (pinfunction "1_1") (pintype "passive"))
    )
    (net (code "57") (name "Net-(DD7-A)") (class "Default")
      (node (ref "DD7") (pin "3") (pinfunction "A_3") (pintype "bidirectional"))
      (node (ref "R32") (pin "2") (pinfunction "2_2") (pintype "passive"))
    )
    (net (code "58") (name "Net-(DD7-B)") (class "Default")
      (node (ref "DD7") (pin "4") (pinfunction "B_4") (pintype "bidirectional"))
      (node (ref "R41") (pin "1") (pinfunction "1_1") (pintype "passive"))
    )
    (net (code "59") (name "Net-(DD8-A)") (class "Default")
      (node (ref "DD8") (pin "3") (pinfunction "A_3") (pintype "bidirectional"))
      (node (ref "R33") (pin "2") (pinfunction "2_2") (pintype "passive"))
    )
    (net (code "60") (name "Net-(DD8-B)") (class "Default")
      (node (ref "DD8") (pin "4") (pinfunction "B_4") (pintype "bidirectional"))
      (node (ref "R42") (pin "1") (pinfunction "1_1") (pintype "passive"))
    )
    (net (code "61") (name "Net-(DD9-B)") (class "Default")
      (node (ref "DD9") (pin "4") (pinfunction "B_4") (pintype "bidirectional"))
      (node (ref "R43") (pin "1") (pinfunction "1_1") (pintype "passive"))
    )
    (net (code "62") (name "Net-(HL1-К)") (class "Default")
      (node (ref "HL1") (pin "2") (pinfunction "К_2") (pintype "passive"))
      (node (ref "R15") (pin "1") (pinfunction "1_1") (pintype "passive"))
    )
    (net (code "63") (name "Net-(HL2-К)") (class "Default")
      (node (ref "HL2") (pin "2") (pinfunction "К_2") (pintype "passive"))
      (node (ref "R16") (pin "1") (pinfunction "1_1") (pintype "passive"))
    )
    (net (code "64") (name "Net-(VT1-D)") (class "Default")
      (node (ref "R27") (pin "1") (pinfunction "1_1") (pintype "passive"))
      (node (ref "VT1") (pin "3") (pinfunction "D_3") (pintype "passive"))
    )
    (net (code "65") (name "TVCC") (class "Default")
      (node (ref "L2") (pin "2") (pinfunction "2_2") (pintype "passive"))
      (node (ref "XP2") (pin "1") (pintype "passive"))
      (node (ref "XS2") (pin "1") (pintype "passive"))
      (node (ref "XS3") (pin "1") (pintype "passive"))
    )
    (net (code "66") (name "unconnected-(DD2A-PA9-Pad42)") (class "Default")
      (node (ref "DD2") (pin "42") (pinfunction "PA9_42") (pintype "bidirectional+no_connect"))
    )
    (net (code "67") (name "unconnected-(DD2A-PA15-Pad50)") (class "Default")
      (node (ref "DD2") (pin "50") (pinfunction "PA15_50") (pintype "bidirectional+no_connect"))
    )
    (net (code "68") (name "unconnected-(DD2A-PB0-Pad26)") (class "Default")
      (node (ref "DD2") (pin "26") (pinfunction "PB0_26") (pintype "bidirectional+no_connect"))
    )
    (net (code "69") (name "unconnected-(DD2A-PB3{slash}SWO-Pad55)") (class "Default")
      (node (ref "DD2") (pin "55") (pinfunction "PB3/SWO_55") (pintype "bidirectional+no_connect"))
    )
    (net (code "70") (name "unconnected-(DD2A-PB4-Pad56)") (class "Default")
      (node (ref "DD2") (pin "56") (pinfunction "PB4_56") (pintype "bidirectional+no_connect"))
    )
    (net (code "71") (name "unconnected-(DD2A-PB5-Pad57)") (class "Default")
      (node (ref "DD2") (pin "57") (pinfunction "PB5_57") (pintype "bidirectional+no_connect"))
    )
    (net (code "72") (name "unconnected-(DD2A-PB6-Pad58)") (class "Default")
      (node (ref "DD2") (pin "58") (pinfunction "PB6_58") (pintype "bidirectional+no_connect"))
    )
    (net (code "73") (name "unconnected-(DD2A-PB7-Pad59)") (class "Default")
      (node (ref "DD2") (pin "59") (pinfunction "PB7_59") (pintype "bidirectional+no_connect"))
    )
    (net (code "74") (name "unconnected-(DD2A-PB9-Pad62)") (class "Default")
      (node (ref "DD2") (pin "62") (pinfunction "PB9_62") (pintype "bidirectional+no_connect"))
    )
    (net (code "75") (name "unconnected-(DD2A-PC4-Pad24)") (class "Default")
      (node (ref "DD2") (pin "24") (pinfunction "PC4_24") (pintype "bidirectional+no_connect"))
    )
    (net (code "76") (name "unconnected-(DD2A-PC10-Pad51)") (class "Default")
      (node (ref "DD2") (pin "51") (pinfunction "PC10_51") (pintype "bidirectional+no_connect"))
    )
    (net (code "77") (name "unconnected-(DD2A-PC11-Pad52)") (class "Default")
      (node (ref "DD2") (pin "52") (pinfunction "PC11_52") (pintype "bidirectional+no_connect"))
    )
    (net (code "78") (name "unconnected-(DD2A-PC13{slash}RTC-Pad2)") (class "Default")
      (node (ref "DD2") (pin "2") (pinfunction "PC13/RTC_2") (pintype "bidirectional+no_connect"))
    )
    (net (code "79") (name "unconnected-(DD2A-PC14{slash}OSC3I-Pad3)") (class "Default")
      (node (ref "DD2") (pin "3") (pinfunction "PC14/OSC3I_3") (pintype "bidirectional+no_connect"))
    )
    (net (code "80") (name "unconnected-(DD2A-PC15{slash}OSC3O-Pad4)") (class "Default")
      (node (ref "DD2") (pin "4") (pinfunction "PC15/OSC3O_4") (pintype "bidirectional+no_connect"))
    )
    (net (code "81") (name "unconnected-(DD2A-PD2-Pad54)") (class "Default")
      (node (ref "DD2") (pin "54") (pinfunction "PD2_54") (pintype "bidirectional+no_connect"))
    )
    (net (code "82") (name "unconnected-(XS3-Pad6)") (class "Default")
      (node (ref "XS3") (pin "6") (pintype "passive+no_connect"))
    )
  )
)
